# LED_Driver_and_LEDs_02.net
KiCad netlist of a schematic drawn in Altium Designer
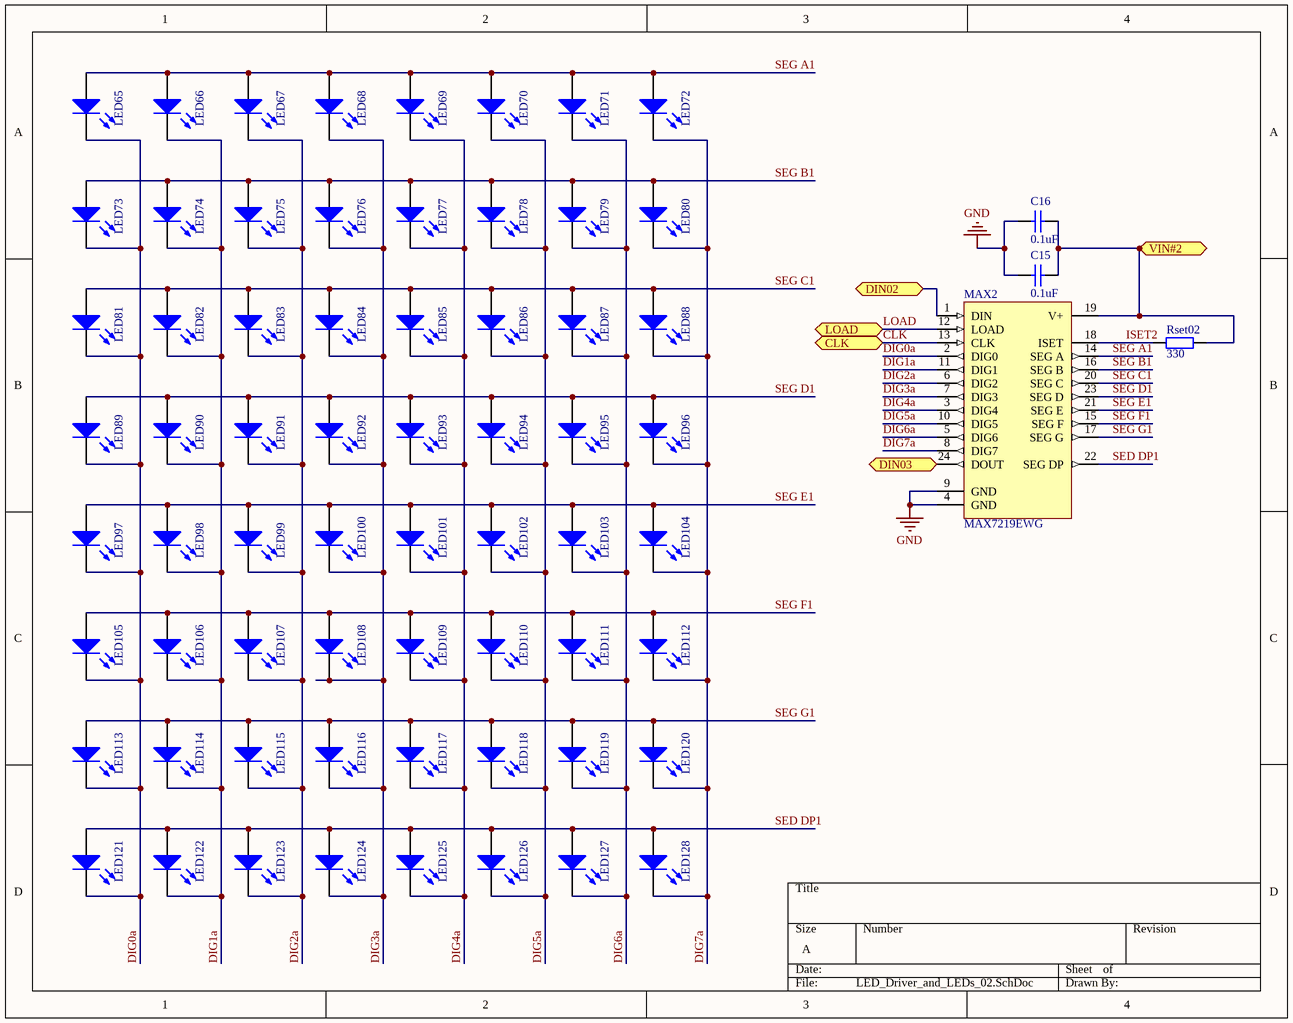
[diagram p0: LED_Driver_and_LEDs_02.SchDoc]

(export (version "E")
  (design (tool "Eeschema 10.0.6"))
  (components
    (comp (ref "C15")
      (value "0.1uF")
      (footprint "6-0805_N")
      (description "Capacitor (Semiconductor SIM Model)")
      (fields (field (name "Comment") "Cap Semi") (field (name "PUBLISHER") "Altium Limited"))
      (libsource (lib "Miscellaneous Devices") (part "Cap Semi"))
    )
    (comp (ref "C16")
      (value "0.1uF")
      (footprint "6-0805_N")
      (description "Capacitor (Semiconductor SIM Model)")
      (fields (field (name "Comment") "Cap Semi") (field (name "PUBLISHER") "Altium Limited"))
      (libsource (lib "Miscellaneous Devices") (part "Cap Semi"))
    )
    (comp (ref "LED65")
      (value "LED3")
      (footprint "3.5X2.8X1.9")
      (description "Typical BLUE SiC LED")
      (fields (field (name "PUBLISHER") "Altium Limited"))
      (libsource (lib "Miscellaneous Devices") (part "LED3"))
    )
    (comp (ref "LED66")
      (value "LED3")
      (footprint "3.5X2.8X1.9")
      (description "Typical BLUE SiC LED")
      (fields (field (name "PUBLISHER") "Altium Limited"))
      (libsource (lib "Miscellaneous Devices") (part "LED3"))
    )
    (comp (ref "LED67")
      (value "LED3")
      (footprint "3.5X2.8X1.9")
      (description "Typical BLUE SiC LED")
      (fields (field (name "PUBLISHER") "Altium Limited"))
      (libsource (lib "Miscellaneous Devices") (part "LED3"))
    )
    (comp (ref "LED68")
      (value "LED3")
      (footprint "3.5X2.8X1.9")
      (description "Typical BLUE SiC LED")
      (fields (field (name "PUBLISHER") "Altium Limited"))
      (libsource (lib "Miscellaneous Devices") (part "LED3"))
    )
    (comp (ref "LED69")
      (value "LED3")
      (footprint "3.5X2.8X1.9")
      (description "Typical BLUE SiC LED")
      (fields (field (name "PUBLISHER") "Altium Limited"))
      (libsource (lib "Miscellaneous Devices") (part "LED3"))
    )
    (comp (ref "LED70")
      (value "LED3")
      (footprint "3.5X2.8X1.9")
      (description "Typical BLUE SiC LED")
      (fields (field (name "PUBLISHER") "Altium Limited"))
      (libsource (lib "Miscellaneous Devices") (part "LED3"))
    )
    (comp (ref "LED71")
      (value "LED3")
      (footprint "3.5X2.8X1.9")
      (description "Typical BLUE SiC LED")
      (fields (field (name "PUBLISHER") "Altium Limited"))
      (libsource (lib "Miscellaneous Devices") (part "LED3"))
    )
    (comp (ref "LED72")
      (value "LED3")
      (footprint "3.5X2.8X1.9")
      (description "Typical BLUE SiC LED")
      (fields (field (name "PUBLISHER") "Altium Limited"))
      (libsource (lib "Miscellaneous Devices") (part "LED3"))
    )
    (comp (ref "LED73")
      (value "LED3")
      (footprint "3.5X2.8X1.9")
      (description "Typical BLUE SiC LED")
      (fields (field (name "PUBLISHER") "Altium Limited"))
      (libsource (lib "Miscellaneous Devices") (part "LED3"))
    )
    (comp (ref "LED74")
      (value "LED3")
      (footprint "3.5X2.8X1.9")
      (description "Typical BLUE SiC LED")
      (fields (field (name "PUBLISHER") "Altium Limited"))
      (libsource (lib "Miscellaneous Devices") (part "LED3"))
    )
    (comp (ref "LED75")
      (value "LED3")
      (footprint "3.5X2.8X1.9")
      (description "Typical BLUE SiC LED")
      (fields (field (name "PUBLISHER") "Altium Limited"))
      (libsource (lib "Miscellaneous Devices") (part "LED3"))
    )
    (comp (ref "LED76")
      (value "LED3")
      (footprint "3.5X2.8X1.9")
      (description "Typical BLUE SiC LED")
      (fields (field (name "PUBLISHER") "Altium Limited"))
      (libsource (lib "Miscellaneous Devices") (part "LED3"))
    )
    (comp (ref "LED77")
      (value "LED3")
      (footprint "3.5X2.8X1.9")
      (description "Typical BLUE SiC LED")
      (fields (field (name "PUBLISHER") "Altium Limited"))
      (libsource (lib "Miscellaneous Devices") (part "LED3"))
    )
    (comp (ref "LED78")
      (value "LED3")
      (footprint "3.5X2.8X1.9")
      (description "Typical BLUE SiC LED")
      (fields (field (name "PUBLISHER") "Altium Limited"))
      (libsource (lib "Miscellaneous Devices") (part "LED3"))
    )
    (comp (ref "LED79")
      (value "LED3")
      (footprint "3.5X2.8X1.9")
      (description "Typical BLUE SiC LED")
      (fields (field (name "PUBLISHER") "Altium Limited"))
      (libsource (lib "Miscellaneous Devices") (part "LED3"))
    )
    (comp (ref "LED80")
      (value "LED3")
      (footprint "3.5X2.8X1.9")
      (description "Typical BLUE SiC LED")
      (fields (field (name "PUBLISHER") "Altium Limited"))
      (libsource (lib "Miscellaneous Devices") (part "LED3"))
    )
    (comp (ref "LED81")
      (value "LED3")
      (footprint "3.5X2.8X1.9")
      (description "Typical BLUE SiC LED")
      (fields (field (name "PUBLISHER") "Altium Limited"))
      (libsource (lib "Miscellaneous Devices") (part "LED3"))
    )
    (comp (ref "LED82")
      (value "LED3")
      (footprint "3.5X2.8X1.9")
      (description "Typical BLUE SiC LED")
      (fields (field (name "PUBLISHER") "Altium Limited"))
      (libsource (lib "Miscellaneous Devices") (part "LED3"))
    )
    (comp (ref "LED83")
      (value "LED3")
      (footprint "3.5X2.8X1.9")
      (description "Typical BLUE SiC LED")
      (fields (field (name "PUBLISHER") "Altium Limited"))
      (libsource (lib "Miscellaneous Devices") (part "LED3"))
    )
    (comp (ref "LED84")
      (value "LED3")
      (footprint "3.5X2.8X1.9")
      (description "Typical BLUE SiC LED")
      (fields (field (name "PUBLISHER") "Altium Limited"))
      (libsource (lib "Miscellaneous Devices") (part "LED3"))
    )
    (comp (ref "LED85")
      (value "LED3")
      (footprint "3.5X2.8X1.9")
      (description "Typical BLUE SiC LED")
      (fields (field (name "PUBLISHER") "Altium Limited"))
      (libsource (lib "Miscellaneous Devices") (part "LED3"))
    )
    (comp (ref "LED86")
      (value "LED3")
      (footprint "3.5X2.8X1.9")
      (description "Typical BLUE SiC LED")
      (fields (field (name "PUBLISHER") "Altium Limited"))
      (libsource (lib "Miscellaneous Devices") (part "LED3"))
    )
    (comp (ref "LED87")
      (value "LED3")
      (footprint "3.5X2.8X1.9")
      (description "Typical BLUE SiC LED")
      (fields (field (name "PUBLISHER") "Altium Limited"))
      (libsource (lib "Miscellaneous Devices") (part "LED3"))
    )
    (comp (ref "LED88")
      (value "LED3")
      (footprint "3.5X2.8X1.9")
      (description "Typical BLUE SiC LED")
      (fields (field (name "PUBLISHER") "Altium Limited"))
      (libsource (lib "Miscellaneous Devices") (part "LED3"))
    )
    (comp (ref "LED89")
      (value "LED3")
      (footprint "3.5X2.8X1.9")
      (description "Typical BLUE SiC LED")
      (fields (field (name "PUBLISHER") "Altium Limited"))
      (libsource (lib "Miscellaneous Devices") (part "LED3"))
    )
    (comp (ref "LED90")
      (value "LED3")
      (footprint "3.5X2.8X1.9")
      (description "Typical BLUE SiC LED")
      (fields (field (name "PUBLISHER") "Altium Limited"))
      (libsource (lib "Miscellaneous Devices") (part "LED3"))
    )
    (comp (ref "LED91")
      (value "LED3")
      (footprint "3.5X2.8X1.9")
      (description "Typical BLUE SiC LED")
      (fields (field (name "PUBLISHER") "Altium Limited"))
      (libsource (lib "Miscellaneous Devices") (part "LED3"))
    )
    (comp (ref "LED92")
      (value "LED3")
      (footprint "3.5X2.8X1.9")
      (description "Typical BLUE SiC LED")
      (fields (field (name "PUBLISHER") "Altium Limited"))
      (libsource (lib "Miscellaneous Devices") (part "LED3"))
    )
    (comp (ref "LED93")
      (value "LED3")
      (footprint "3.5X2.8X1.9")
      (description "Typical BLUE SiC LED")
      (fields (field (name "PUBLISHER") "Altium Limited"))
      (libsource (lib "Miscellaneous Devices") (part "LED3"))
    )
    (comp (ref "LED94")
      (value "LED3")
      (footprint "3.5X2.8X1.9")
      (description "Typical BLUE SiC LED")
      (fields (field (name "PUBLISHER") "Altium Limited"))
      (libsource (lib "Miscellaneous Devices") (part "LED3"))
    )
    (comp (ref "LED95")
      (value "LED3")
      (footprint "3.5X2.8X1.9")
      (description "Typical BLUE SiC LED")
      (fields (field (name "PUBLISHER") "Altium Limited"))
      (libsource (lib "Miscellaneous Devices") (part "LED3"))
    )
    (comp (ref "LED96")
      (value "LED3")
      (footprint "3.5X2.8X1.9")
      (description "Typical BLUE SiC LED")
      (fields (field (name "PUBLISHER") "Altium Limited"))
      (libsource (lib "Miscellaneous Devices") (part "LED3"))
    )
    (comp (ref "LED97")
      (value "LED3")
      (footprint "3.5X2.8X1.9")
      (description "Typical BLUE SiC LED")
      (fields (field (name "PUBLISHER") "Altium Limited"))
      (libsource (lib "Miscellaneous Devices") (part "LED3"))
    )
    (comp (ref "LED98")
      (value "LED3")
      (footprint "3.5X2.8X1.9")
      (description "Typical BLUE SiC LED")
      (fields (field (name "PUBLISHER") "Altium Limited"))
      (libsource (lib "Miscellaneous Devices") (part "LED3"))
    )
    (comp (ref "LED99")
      (value "LED3")
      (footprint "3.5X2.8X1.9")
      (description "Typical BLUE SiC LED")
      (fields (field (name "PUBLISHER") "Altium Limited"))
      (libsource (lib "Miscellaneous Devices") (part "LED3"))
    )
    (comp (ref "LED100")
      (value "LED3")
      (footprint "3.5X2.8X1.9")
      (description "Typical BLUE SiC LED")
      (fields (field (name "PUBLISHER") "Altium Limited"))
      (libsource (lib "Miscellaneous Devices") (part "LED3"))
    )
    (comp (ref "LED101")
      (value "LED3")
      (footprint "3.5X2.8X1.9")
      (description "Typical BLUE SiC LED")
      (fields (field (name "PUBLISHER") "Altium Limited"))
      (libsource (lib "Miscellaneous Devices") (part "LED3"))
    )
    (comp (ref "LED102")
      (value "LED3")
      (footprint "3.5X2.8X1.9")
      (description "Typical BLUE SiC LED")
      (fields (field (name "PUBLISHER") "Altium Limited"))
      (libsource (lib "Miscellaneous Devices") (part "LED3"))
    )
    (comp (ref "LED103")
      (value "LED3")
      (footprint "3.5X2.8X1.9")
      (description "Typical BLUE SiC LED")
      (fields (field (name "PUBLISHER") "Altium Limited"))
      (libsource (lib "Miscellaneous Devices") (part "LED3"))
    )
    (comp (ref "LED104")
      (value "LED3")
      (footprint "3.5X2.8X1.9")
      (description "Typical BLUE SiC LED")
      (fields (field (name "PUBLISHER") "Altium Limited"))
      (libsource (lib "Miscellaneous Devices") (part "LED3"))
    )
    (comp (ref "LED105")
      (value "LED3")
      (footprint "3.5X2.8X1.9")
      (description "Typical BLUE SiC LED")
      (fields (field (name "PUBLISHER") "Altium Limited"))
      (libsource (lib "Miscellaneous Devices") (part "LED3"))
    )
    (comp (ref "LED106")
      (value "LED3")
      (footprint "3.5X2.8X1.9")
      (description "Typical BLUE SiC LED")
      (fields (field (name "PUBLISHER") "Altium Limited"))
      (libsource (lib "Miscellaneous Devices") (part "LED3"))
    )
    (comp (ref "LED107")
      (value "LED3")
      (footprint "3.5X2.8X1.9")
      (description "Typical BLUE SiC LED")
      (fields (field (name "PUBLISHER") "Altium Limited"))
      (libsource (lib "Miscellaneous Devices") (part "LED3"))
    )
    (comp (ref "LED108")
      (value "LED3")
      (footprint "3.5X2.8X1.9")
      (description "Typical BLUE SiC LED")
      (fields (field (name "PUBLISHER") "Altium Limited"))
      (libsource (lib "Miscellaneous Devices") (part "LED3"))
    )
    (comp (ref "LED109")
      (value "LED3")
      (footprint "3.5X2.8X1.9")
      (description "Typical BLUE SiC LED")
      (fields (field (name "PUBLISHER") "Altium Limited"))
      (libsource (lib "Miscellaneous Devices") (part "LED3"))
    )
    (comp (ref "LED110")
      (value "LED3")
      (footprint "3.5X2.8X1.9")
      (description "Typical BLUE SiC LED")
      (fields (field (name "PUBLISHER") "Altium Limited"))
      (libsource (lib "Miscellaneous Devices") (part "LED3"))
    )
    (comp (ref "LED111")
      (value "LED3")
      (footprint "3.5X2.8X1.9")
      (description "Typical BLUE SiC LED")
      (fields (field (name "PUBLISHER") "Altium Limited"))
      (libsource (lib "Miscellaneous Devices") (part "LED3"))
    )
    (comp (ref "LED112")
      (value "LED3")
      (footprint "3.5X2.8X1.9")
      (description "Typical BLUE SiC LED")
      (fields (field (name "PUBLISHER") "Altium Limited"))
      (libsource (lib "Miscellaneous Devices") (part "LED3"))
    )
    (comp (ref "LED113")
      (value "LED3")
      (footprint "3.5X2.8X1.9")
      (description "Typical BLUE SiC LED")
      (fields (field (name "PUBLISHER") "Altium Limited"))
      (libsource (lib "Miscellaneous Devices") (part "LED3"))
    )
    (comp (ref "LED114")
      (value "LED3")
      (footprint "3.5X2.8X1.9")
      (description "Typical BLUE SiC LED")
      (fields (field (name "PUBLISHER") "Altium Limited"))
      (libsource (lib "Miscellaneous Devices") (part "LED3"))
    )
    (comp (ref "LED115")
      (value "LED3")
      (footprint "3.5X2.8X1.9")
      (description "Typical BLUE SiC LED")
      (fields (field (name "PUBLISHER") "Altium Limited"))
      (libsource (lib "Miscellaneous Devices") (part "LED3"))
    )
    (comp (ref "LED116")
      (value "LED3")
      (footprint "3.5X2.8X1.9")
      (description "Typical BLUE SiC LED")
      (fields (field (name "PUBLISHER") "Altium Limited"))
      (libsource (lib "Miscellaneous Devices") (part "LED3"))
    )
    (comp (ref "LED117")
      (value "LED3")
      (footprint "3.5X2.8X1.9")
      (description "Typical BLUE SiC LED")
      (fields (field (name "PUBLISHER") "Altium Limited"))
      (libsource (lib "Miscellaneous Devices") (part "LED3"))
    )
    (comp (ref "LED118")
      (value "LED3")
      (footprint "3.5X2.8X1.9")
      (description "Typical BLUE SiC LED")
      (fields (field (name "PUBLISHER") "Altium Limited"))
      (libsource (lib "Miscellaneous Devices") (part "LED3"))
    )
    (comp (ref "LED119")
      (value "LED3")
      (footprint "3.5X2.8X1.9")
      (description "Typical BLUE SiC LED")
      (fields (field (name "PUBLISHER") "Altium Limited"))
      (libsource (lib "Miscellaneous Devices") (part "LED3"))
    )
    (comp (ref "LED120")
      (value "LED3")
      (footprint "3.5X2.8X1.9")
      (description "Typical BLUE SiC LED")
      (fields (field (name "PUBLISHER") "Altium Limited"))
      (libsource (lib "Miscellaneous Devices") (part "LED3"))
    )
    (comp (ref "LED121")
      (value "LED3")
      (footprint "3.5X2.8X1.9")
      (description "Typical BLUE SiC LED")
      (fields (field (name "PUBLISHER") "Altium Limited"))
      (libsource (lib "Miscellaneous Devices") (part "LED3"))
    )
    (comp (ref "LED122")
      (value "LED3")
      (footprint "3.5X2.8X1.9")
      (description "Typical BLUE SiC LED")
      (fields (field (name "PUBLISHER") "Altium Limited"))
      (libsource (lib "Miscellaneous Devices") (part "LED3"))
    )
    (comp (ref "LED123")
      (value "LED3")
      (footprint "3.5X2.8X1.9")
      (description "Typical BLUE SiC LED")
      (fields (field (name "PUBLISHER") "Altium Limited"))
      (libsource (lib "Miscellaneous Devices") (part "LED3"))
    )
    (comp (ref "LED124")
      (value "LED3")
      (footprint "3.5X2.8X1.9")
      (description "Typical BLUE SiC LED")
      (fields (field (name "PUBLISHER") "Altium Limited"))
      (libsource (lib "Miscellaneous Devices") (part "LED3"))
    )
    (comp (ref "LED125")
      (value "LED3")
      (footprint "3.5X2.8X1.9")
      (description "Typical BLUE SiC LED")
      (fields (field (name "PUBLISHER") "Altium Limited"))
      (libsource (lib "Miscellaneous Devices") (part "LED3"))
    )
    (comp (ref "LED126")
      (value "LED3")
      (footprint "3.5X2.8X1.9")
      (description "Typical BLUE SiC LED")
      (fields (field (name "PUBLISHER") "Altium Limited"))
      (libsource (lib "Miscellaneous Devices") (part "LED3"))
    )
    (comp (ref "LED127")
      (value "LED3")
      (footprint "3.5X2.8X1.9")
      (description "Typical BLUE SiC LED")
      (fields (field (name "PUBLISHER") "Altium Limited"))
      (libsource (lib "Miscellaneous Devices") (part "LED3"))
    )
    (comp (ref "LED128")
      (value "LED3")
      (footprint "3.5X2.8X1.9")
      (description "Typical BLUE SiC LED")
      (fields (field (name "PUBLISHER") "Altium Limited"))
      (libsource (lib "Miscellaneous Devices") (part "LED3"))
    )
    (comp (ref "MAX2")
      (value "MAX7219EWG")
      (footprint "WSO24_N")
      (description "Serially Interfaced, 8-Digit LED Display Driver")
      (fields (field (name "PUBLISHER") "Altium Limited"))
      (libsource (lib "Maxim Interface Display Driver") (part "MAX7219EWG"))
    )
    (comp (ref "Rset02")
      (value "330")
      (footprint "J1-0603")
      (description "Resistor")
      (fields (field (name "Comment") "Res2") (field (name "PUBLISHER") "Altium Limited"))
      (libsource (lib "Miscellaneous Devices") (part "Res2"))
    )
  )
  (nets
    (net (code "1") (name "/CLK") (class "Default")
      (node (ref "MAX2") (pin "13") (pinfunction "CLK_13") (pintype "input"))
    )
    (net (code "2") (name "/DIG0a") (class "Default")
      (node (ref "LED105") (pin "2") (pinfunction "K_2") (pintype "passive"))
      (node (ref "LED113") (pin "2") (pinfunction "K_2") (pintype "passive"))
      (node (ref "LED121") (pin "2") (pinfunction "K_2") (pintype "passive"))
      (node (ref "LED65") (pin "2") (pinfunction "K_2") (pintype "passive"))
      (node (ref "LED73") (pin "2") (pinfunction "K_2") (pintype "passive"))
      (node (ref "LED81") (pin "2") (pinfunction "K_2") (pintype "passive"))
      (node (ref "LED89") (pin "2") (pinfunction "K_2") (pintype "passive"))
      (node (ref "LED97") (pin "2") (pinfunction "K_2") (pintype "passive"))
      (node (ref "MAX2") (pin "2") (pinfunction "DIG0_2") (pintype "output"))
    )
    (net (code "3") (name "/DIG1a") (class "Default")
      (node (ref "LED106") (pin "2") (pinfunction "K_2") (pintype "passive"))
      (node (ref "LED114") (pin "2") (pinfunction "K_2") (pintype "passive"))
      (node (ref "LED122") (pin "2") (pinfunction "K_2") (pintype "passive"))
      (node (ref "LED66") (pin "2") (pinfunction "K_2") (pintype "passive"))
      (node (ref "LED74") (pin "2") (pinfunction "K_2") (pintype "passive"))
      (node (ref "LED82") (pin "2") (pinfunction "K_2") (pintype "passive"))
      (node (ref "LED90") (pin "2") (pinfunction "K_2") (pintype "passive"))
      (node (ref "LED98") (pin "2") (pinfunction "K_2") (pintype "passive"))
      (node (ref "MAX2") (pin "11") (pinfunction "DIG1_11") (pintype "output"))
    )
    (net (code "4") (name "/DIG2a") (class "Default")
      (node (ref "LED107") (pin "2") (pinfunction "K_2") (pintype "passive"))
      (node (ref "LED115") (pin "2") (pinfunction "K_2") (pintype "passive"))
      (node (ref "LED123") (pin "2") (pinfunction "K_2") (pintype "passive"))
      (node (ref "LED67") (pin "2") (pinfunction "K_2") (pintype "passive"))
      (node (ref "LED75") (pin "2") (pinfunction "K_2") (pintype "passive"))
      (node (ref "LED83") (pin "2") (pinfunction "K_2") (pintype "passive"))
      (node (ref "LED91") (pin "2") (pinfunction "K_2") (pintype "passive"))
      (node (ref "LED99") (pin "2") (pinfunction "K_2") (pintype "passive"))
      (node (ref "MAX2") (pin "6") (pinfunction "DIG2_6") (pintype "output"))
    )
    (net (code "5") (name "/DIG3a") (class "Default")
      (node (ref "LED100") (pin "2") (pinfunction "K_2") (pintype "passive"))
      (node (ref "LED108") (pin "2") (pinfunction "K_2") (pintype "passive"))
      (node (ref "LED116") (pin "2") (pinfunction "K_2") (pintype "passive"))
      (node (ref "LED124") (pin "2") (pinfunction "K_2") (pintype "passive"))
      (node (ref "LED68") (pin "2") (pinfunction "K_2") (pintype "passive"))
      (node (ref "LED76") (pin "2") (pinfunction "K_2") (pintype "passive"))
      (node (ref "LED84") (pin "2") (pinfunction "K_2") (pintype "passive"))
      (node (ref "LED92") (pin "2") (pinfunction "K_2") (pintype "passive"))
      (node (ref "MAX2") (pin "7") (pinfunction "DIG3_7") (pintype "output"))
    )
    (net (code "6") (name "/DIG4a") (class "Default")
      (node (ref "LED101") (pin "2") (pinfunction "K_2") (pintype "passive"))
      (node (ref "LED109") (pin "2") (pinfunction "K_2") (pintype "passive"))
      (node (ref "LED117") (pin "2") (pinfunction "K_2") (pintype "passive"))
      (node (ref "LED125") (pin "2") (pinfunction "K_2") (pintype "passive"))
      (node (ref "LED69") (pin "2") (pinfunction "K_2") (pintype "passive"))
      (node (ref "LED77") (pin "2") (pinfunction "K_2") (pintype "passive"))
      (node (ref "LED85") (pin "2") (pinfunction "K_2") (pintype "passive"))
      (node (ref "LED93") (pin "2") (pinfunction "K_2") (pintype "passive"))
      (node (ref "MAX2") (pin "3") (pinfunction "DIG4_3") (pintype "output"))
    )
    (net (code "7") (name "/DIG5a") (class "Default")
      (node (ref "LED102") (pin "2") (pinfunction "K_2") (pintype "passive"))
      (node (ref "LED110") (pin "2") (pinfunction "K_2") (pintype "passive"))
      (node (ref "LED118") (pin "2") (pinfunction "K_2") (pintype "passive"))
      (node (ref "LED126") (pin "2") (pinfunction "K_2") (pintype "passive"))
      (node (ref "LED70") (pin "2") (pinfunction "K_2") (pintype "passive"))
      (node (ref "LED78") (pin "2") (pinfunction "K_2") (pintype "passive"))
      (node (ref "LED86") (pin "2") (pinfunction "K_2") (pintype "passive"))
      (node (ref "LED94") (pin "2") (pinfunction "K_2") (pintype "passive"))
      (node (ref "MAX2") (pin "10") (pinfunction "DIG5_10") (pintype "output"))
    )
    (net (code "8") (name "/DIG6a") (class "Default")
      (node (ref "LED103") (pin "2") (pinfunction "K_2") (pintype "passive"))
      (node (ref "LED111") (pin "2") (pinfunction "K_2") (pintype "passive"))
      (node (ref "LED119") (pin "2") (pinfunction "K_2") (pintype "passive"))
      (node (ref "LED127") (pin "2") (pinfunction "K_2") (pintype "passive"))
      (node (ref "LED71") (pin "2") (pinfunction "K_2") (pintype "passive"))
      (node (ref "LED79") (pin "2") (pinfunction "K_2") (pintype "passive"))
      (node (ref "LED87") (pin "2") (pinfunction "K_2") (pintype "passive"))
      (node (ref "LED95") (pin "2") (pinfunction "K_2") (pintype "passive"))
      (node (ref "MAX2") (pin "5") (pinfunction "DIG6_5") (pintype "output"))
    )
    (net (code "9") (name "/DIG7a") (class "Default")
      (node (ref "LED104") (pin "2") (pinfunction "K_2") (pintype "passive"))
      (node (ref "LED112") (pin "2") (pinfunction "K_2") (pintype "passive"))
      (node (ref "LED120") (pin "2") (pinfunction "K_2") (pintype "passive"))
      (node (ref "LED128") (pin "2") (pinfunction "K_2") (pintype "passive"))
      (node (ref "LED72") (pin "2") (pinfunction "K_2") (pintype "passive"))
      (node (ref "LED80") (pin "2") (pinfunction "K_2") (pintype "passive"))
      (node (ref "LED88") (pin "2") (pinfunction "K_2") (pintype "passive"))
      (node (ref "LED96") (pin "2") (pinfunction "K_2") (pintype "passive"))
      (node (ref "MAX2") (pin "8") (pinfunction "DIG7_8") (pintype "output"))
    )
    (net (code "10") (name "/DIN02") (class "Default")
      (node (ref "MAX2") (pin "1") (pinfunction "DIN_1") (pintype "input"))
    )
    (net (code "11") (name "/DIN03") (class "Default")
      (node (ref "MAX2") (pin "24") (pinfunction "DOUT_24") (pintype "output"))
    )
    (net (code "12") (name "/ISET2") (class "Default")
      (node (ref "MAX2") (pin "18") (pinfunction "ISET_18") (pintype "passive"))
      (node (ref "Rset02") (pin "2") (pinfunction "2_2") (pintype "passive"))
    )
    (net (code "13") (name "/LOAD") (class "Default")
      (node (ref "MAX2") (pin "12") (pinfunction "LOAD_12") (pintype "input"))
    )
    (net (code "14") (name "/SED DP1") (class "Default")
      (node (ref "LED121") (pin "1") (pinfunction "A_1") (pintype "passive"))
      (node (ref "LED122") (pin "1") (pinfunction "A_1") (pintype "passive"))
      (node (ref "LED123") (pin "1") (pinfunction "A_1") (pintype "passive"))
      (node (ref "LED124") (pin "1") (pinfunction "A_1") (pintype "passive"))
      (node (ref "LED125") (pin "1") (pinfunction "A_1") (pintype "passive"))
      (node (ref "LED126") (pin "1") (pinfunction "A_1") (pintype "passive"))
      (node (ref "LED127") (pin "1") (pinfunction "A_1") (pintype "passive"))
      (node (ref "LED128") (pin "1") (pinfunction "A_1") (pintype "passive"))
      (node (ref "MAX2") (pin "22") (pinfunction "SEG_DP_22") (pintype "output"))
    )
    (net (code "15") (name "/SEG A1") (class "Default")
      (node (ref "LED65") (pin "1") (pinfunction "A_1") (pintype "passive"))
      (node (ref "LED66") (pin "1") (pinfunction "A_1") (pintype "passive"))
      (node (ref "LED67") (pin "1") (pinfunction "A_1") (pintype "passive"))
      (node (ref "LED68") (pin "1") (pinfunction "A_1") (pintype "passive"))
      (node (ref "LED69") (pin "1") (pinfunction "A_1") (pintype "passive"))
      (node (ref "LED70") (pin "1") (pinfunction "A_1") (pintype "passive"))
      (node (ref "LED71") (pin "1") (pinfunction "A_1") (pintype "passive"))
      (node (ref "LED72") (pin "1") (pinfunction "A_1") (pintype "passive"))
      (node (ref "MAX2") (pin "14") (pinfunction "SEG_A_14") (pintype "output"))
    )
    (net (code "16") (name "/SEG B1") (class "Default")
      (node (ref "LED73") (pin "1") (pinfunction "A_1") (pintype "passive"))
      (node (ref "LED74") (pin "1") (pinfunction "A_1") (pintype "passive"))
      (node (ref "LED75") (pin "1") (pinfunction "A_1") (pintype "passive"))
      (node (ref "LED76") (pin "1") (pinfunction "A_1") (pintype "passive"))
      (node (ref "LED77") (pin "1") (pinfunction "A_1") (pintype "passive"))
      (node (ref "LED78") (pin "1") (pinfunction "A_1") (pintype "passive"))
      (node (ref "LED79") (pin "1") (pinfunction "A_1") (pintype "passive"))
      (node (ref "LED80") (pin "1") (pinfunction "A_1") (pintype "passive"))
      (node (ref "MAX2") (pin "16") (pinfunction "SEG_B_16") (pintype "output"))
    )
    (net (code "17") (name "/SEG C1") (class "Default")
      (node (ref "LED81") (pin "1") (pinfunction "A_1") (pintype "passive"))
      (node (ref "LED82") (pin "1") (pinfunction "A_1") (pintype "passive"))
      (node (ref "LED83") (pin "1") (pinfunction "A_1") (pintype "passive"))
      (node (ref "LED84") (pin "1") (pinfunction "A_1") (pintype "passive"))
      (node (ref "LED85") (pin "1") (pinfunction "A_1") (pintype "passive"))
      (node (ref "LED86") (pin "1") (pinfunction "A_1") (pintype "passive"))
      (node (ref "LED87") (pin "1") (pinfunction "A_1") (pintype "passive"))
      (node (ref "LED88") (pin "1") (pinfunction "A_1") (pintype "passive"))
      (node (ref "MAX2") (pin "20") (pinfunction "SEG_C_20") (pintype "output"))
    )
    (net (code "18") (name "/SEG D1") (class "Default")
      (node (ref "LED89") (pin "1") (pinfunction "A_1") (pintype "passive"))
      (node (ref "LED90") (pin "1") (pinfunction "A_1") (pintype "passive"))
      (node (ref "LED91") (pin "1") (pinfunction "A_1") (pintype "passive"))
      (node (ref "LED92") (pin "1") (pinfunction "A_1") (pintype "passive"))
      (node (ref "LED93") (pin "1") (pinfunction "A_1") (pintype "passive"))
      (node (ref "LED94") (pin "1") (pinfunction "A_1") (pintype "passive"))
      (node (ref "LED95") (pin "1") (pinfunction "A_1") (pintype "passive"))
      (node (ref "LED96") (pin "1") (pinfunction "A_1") (pintype "passive"))
      (node (ref "MAX2") (pin "23") (pinfunction "SEG_D_23") (pintype "output"))
    )
    (net (code "19") (name "/SEG E1") (class "Default")
      (node (ref "LED100") (pin "1") (pinfunction "A_1") (pintype "passive"))
      (node (ref "LED101") (pin "1") (pinfunction "A_1") (pintype "passive"))
      (node (ref "LED102") (pin "1") (pinfunction "A_1") (pintype "passive"))
      (node (ref "LED103") (pin "1") (pinfunction "A_1") (pintype "passive"))
      (node (ref "LED104") (pin "1") (pinfunction "A_1") (pintype "passive"))
      (node (ref "LED97") (pin "1") (pinfunction "A_1") (pintype "passive"))
      (node (ref "LED98") (pin "1") (pinfunction "A_1") (pintype "passive"))
      (node (ref "LED99") (pin "1") (pinfunction "A_1") (pintype "passive"))
      (node (ref "MAX2") (pin "21") (pinfunction "SEG_E_21") (pintype "output"))
    )
    (net (code "20") (name "/SEG F1") (class "Default")
      (node (ref "LED105") (pin "1") (pinfunction "A_1") (pintype "passive"))
      (node (ref "LED106") (pin "1") (pinfunction "A_1") (pintype "passive"))
      (node (ref "LED107") (pin "1") (pinfunction "A_1") (pintype "passive"))
      (node (ref "LED108") (pin "1") (pinfunction "A_1") (pintype "passive"))
      (node (ref "LED109") (pin "1") (pinfunction "A_1") (pintype "passive"))
      (node (ref "LED110") (pin "1") (pinfunction "A_1") (pintype "passive"))
      (node (ref "LED111") (pin "1") (pinfunction "A_1") (pintype "passive"))
      (node (ref "LED112") (pin "1") (pinfunction "A_1") (pintype "passive"))
      (node (ref "MAX2") (pin "15") (pinfunction "SEG_F_15") (pintype "output"))
    )
    (net (code "21") (name "/SEG G1") (class "Default")
      (node (ref "LED113") (pin "1") (pinfunction "A_1") (pintype "passive"))
      (node (ref "LED114") (pin "1") (pinfunction "A_1") (pintype "passive"))
      (node (ref "LED115") (pin "1") (pinfunction "A_1") (pintype "passive"))
      (node (ref "LED116") (pin "1") (pinfunction "A_1") (pintype "passive"))
      (node (ref "LED117") (pin "1") (pinfunction "A_1") (pintype "passive"))
      (node (ref "LED118") (pin "1") (pinfunction "A_1") (pintype "passive"))
      (node (ref "LED119") (pin "1") (pinfunction "A_1") (pintype "passive"))
      (node (ref "LED120") (pin "1") (pinfunction "A_1") (pintype "passive"))
      (node (ref "MAX2") (pin "17") (pinfunction "SEG_G_17") (pintype "output"))
    )
    (net (code "22") (name "/VIN#2") (class "Default")
      (node (ref "C15") (pin "1") (pinfunction "1_1") (pintype "passive"))
      (node (ref "C16") (pin "1") (pinfunction "1_1") (pintype "passive"))
      (node (ref "MAX2") (pin "19") (pinfunction "V+_19") (pintype "power_in"))
      (node (ref "Rset02") (pin "1") (pinfunction "1_1") (pintype "passive"))
    )
    (net (code "23") (name "GND") (class "Default")
      (node (ref "C15") (pin "2") (pinfunction "2_2") (pintype "passive"))
      (node (ref "C16") (pin "2") (pinfunction "2_2") (pintype "passive"))
      (node (ref "MAX2") (pin "4") (pinfunction "GND_4") (pintype "power_in"))
      (node (ref "MAX2") (pin "9") (pinfunction "GND_9") (pintype "power_in"))
    )
  )
)
